# HumTemp_ESP32.net
KiCad netlist of a schematic drawn in Altium Designer
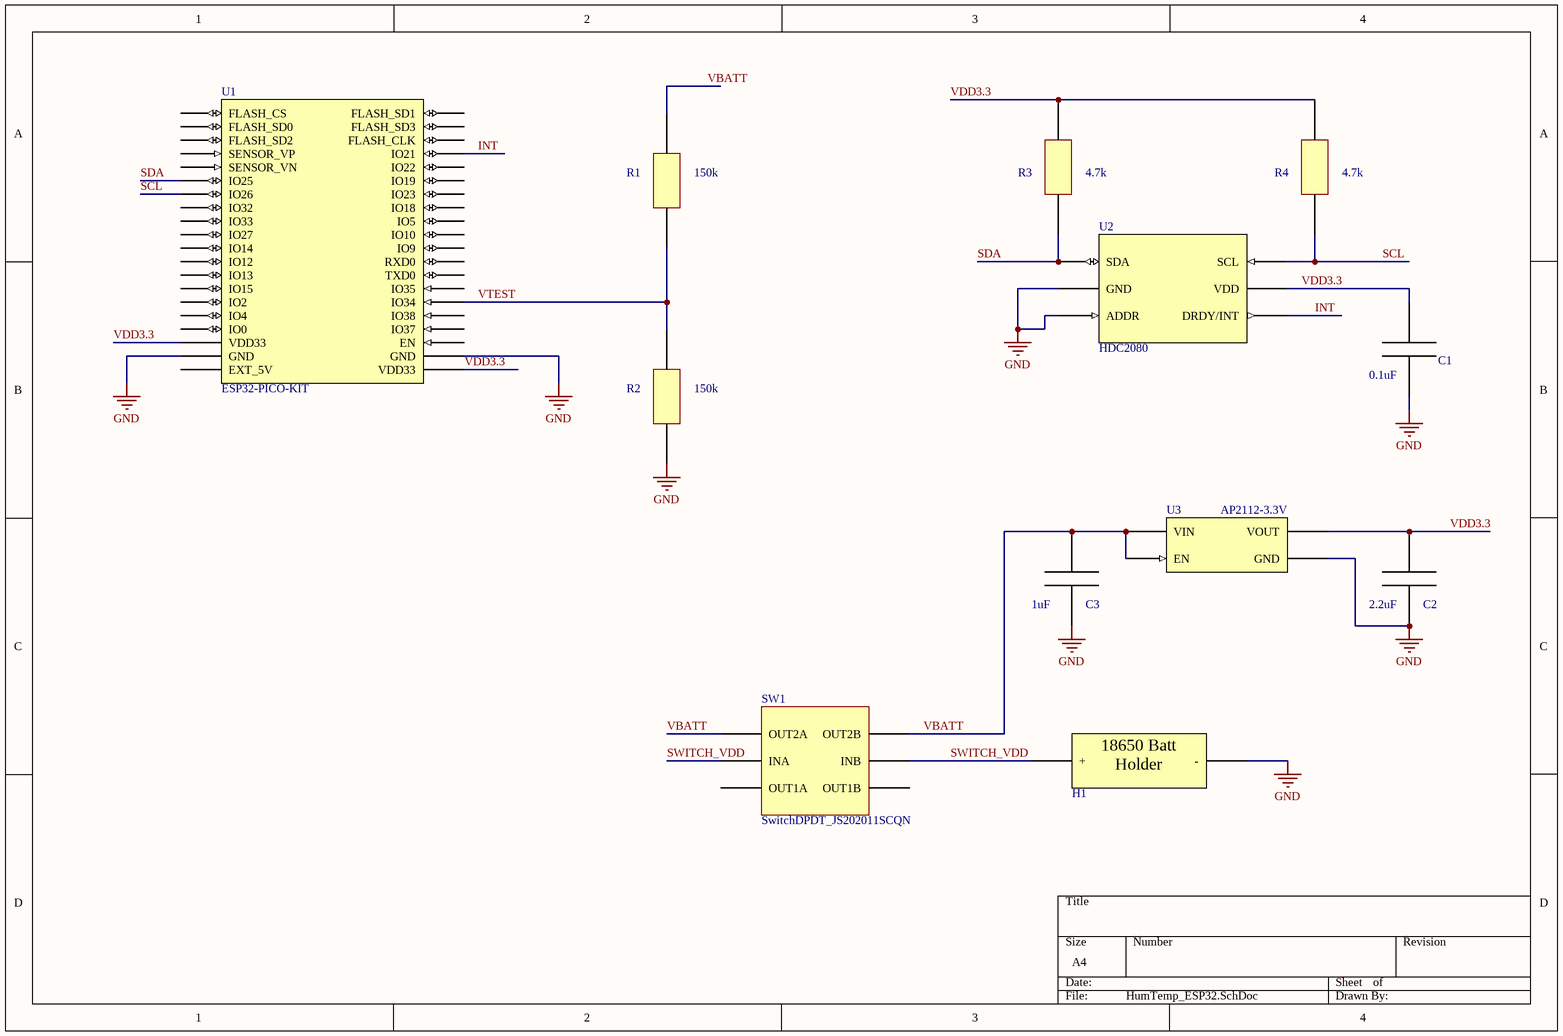
[diagram p0: HumTemp_ESP32.SchDoc]

(export (version "E")
  (design (tool "Eeschema 10.0.6"))
  (components
    (comp (ref "C1")
      (value "0.1uF")
      (footprint "CAPCERAMIC_SMD_2012M_0805I")
      (description "Ceramic SMD capacitor")
      (fields (field (name "Comment") "SMD Capacitor"))
      (libsource (lib "Capacitors") (part "capceramic_SMD"))
    )
    (comp (ref "C2")
      (value "2.2uF")
      (footprint "CAPCERAMIC_SMD_2012M_0805I")
      (description "Ceramic SMD capacitor")
      (fields (field (name "Comment") "SMD Capacitor"))
      (libsource (lib "Capacitors") (part "capceramic_SMD"))
    )
    (comp (ref "C3")
      (value "1uF")
      (footprint "CAPCERAMIC_SMD_2012M_0805I")
      (description "Ceramic SMD capacitor")
      (fields (field (name "Comment") "SMD Capacitor"))
      (libsource (lib "Capacitors") (part "capceramic_SMD"))
    )
    (comp (ref "H1")
      (value "18650 Battery holder - Keystone")
      (footprint "18650_BATTERYHOLDER")
      (libsource (lib "Connectors") (part "18650 Battery holder - Keystone"))
    )
    (comp (ref "R1")
      (value "150k")
      (footprint "RES_SMD_2012M-0805I")
      (fields (field (name "Comment") "SMD Resistor"))
      (libsource (lib "Resistors") (part "resistor_SMD"))
    )
    (comp (ref "R2")
      (value "150k")
      (footprint "RES_SMD_2012M-0805I")
      (fields (field (name "Comment") "SMD Resistor"))
      (libsource (lib "Resistors") (part "resistor_SMD"))
    )
    (comp (ref "R3")
      (value "4.7k")
      (footprint "RES_SMD_2012M-0805I")
      (fields (field (name "Comment") "SMD Resistor"))
      (libsource (lib "Resistors") (part "resistor_SMD"))
    )
    (comp (ref "R4")
      (value "4.7k")
      (footprint "RES_SMD_2012M-0805I")
      (fields (field (name "Comment") "SMD Resistor"))
      (libsource (lib "Resistors") (part "resistor_SMD"))
    )
    (comp (ref "SW1")
      (value "SwitchDPDT_JS202011SCQN")
      (footprint "SWITCHDPDT")
      (libsource (lib "Miscellaneous") (part "SwitchDPDT_JS202011SCQN"))
    )
    (comp (ref "U1")
      (value "ESP32-PICO-KIT")
      (footprint "ESP32-PICO-KIT")
      (libsource (lib "DevBoards") (part "ESP32-PICO-KIT"))
    )
    (comp (ref "U2")
      (value "HDC2080")
      (footprint "WSON6")
      (description "High precision humidity and temperature sensor")
      (libsource (lib "Sensors") (part "HDC2080"))
    )
    (comp (ref "U3")
      (value "AP2112-3.3V")
      (footprint "SOT95P285X110-5M")
      (description "AP2112 - 3.3V voltage regulator")
      (libsource (lib "Power_management") (part "AP2112-3.3V"))
    )
  )
  (nets
    (net (code "1") (name "/INT") (class "Default")
      (node (ref "U1") (pin "24") (pinfunction "IO21_24") (pintype "bidirectional"))
      (node (ref "U2") (pin "4") (pinfunction "DRDY/INT_4") (pintype "output"))
    )
    (net (code "2") (name "/SCL") (class "Default")
      (node (ref "R4") (pin "1") (pinfunction "1_1") (pintype "passive"))
      (node (ref "U1") (pin "7") (pinfunction "IO26_7") (pintype "bidirectional"))
      (node (ref "U2") (pin "6") (pinfunction "SCL_6") (pintype "input"))
    )
    (net (code "3") (name "/SDA") (class "Default")
      (node (ref "R3") (pin "1") (pinfunction "1_1") (pintype "passive"))
      (node (ref "U1") (pin "6") (pinfunction "IO25_6") (pintype "bidirectional"))
      (node (ref "U2") (pin "1") (pinfunction "SDA_1") (pintype "bidirectional"))
    )
    (net (code "4") (name "/SWITCH_VDD") (class "Default")
      (node (ref "H1") (pin "2") (pinfunction "+_2") (pintype "power_in"))
      (node (ref "SW1") (pin "1") (pinfunction "INA_1") (pintype "power_in"))
      (node (ref "SW1") (pin "4") (pinfunction "INB_4") (pintype "power_in"))
    )
    (net (code "5") (name "/VBATT") (class "Default")
      (node (ref "C3") (pin "2") (pinfunction "2_2") (pintype "passive"))
      (node (ref "R1") (pin "2") (pinfunction "2_2") (pintype "passive"))
      (node (ref "SW1") (pin "2") (pinfunction "OUT2A_2") (pintype "power_in"))
      (node (ref "SW1") (pin "5") (pinfunction "OUT2B_5") (pintype "power_in"))
      (node (ref "U3") (pin "1") (pinfunction "VIN_1") (pintype "power_in"))
      (node (ref "U3") (pin "3") (pinfunction "EN_3") (pintype "input"))
    )
    (net (code "6") (name "/VDD3.3") (class "Default")
      (node (ref "C1") (pin "2") (pinfunction "2_2") (pintype "passive"))
      (node (ref "C2") (pin "2") (pinfunction "2_2") (pintype "passive"))
      (node (ref "R3") (pin "2") (pinfunction "2_2") (pintype "passive"))
      (node (ref "R4") (pin "2") (pinfunction "2_2") (pintype "passive"))
      (node (ref "U1") (pin "18") (pinfunction "VDD33_18") (pintype "power_in"))
      (node (ref "U1") (pin "40") (pinfunction "VDD33_40") (pintype "power_in"))
      (node (ref "U2") (pin "5") (pinfunction "VDD_5") (pintype "power_in"))
      (node (ref "U3") (pin "5") (pinfunction "VOUT_5") (pintype "power_in"))
    )
    (net (code "7") (name "/VTEST") (class "Default")
      (node (ref "R1") (pin "1") (pinfunction "1_1") (pintype "passive"))
      (node (ref "R2") (pin "2") (pinfunction "2_2") (pintype "passive"))
      (node (ref "U1") (pin "35") (pinfunction "IO34_35") (pintype "input"))
    )
    (net (code "8") (name "GND") (class "Default")
      (node (ref "C1") (pin "1") (pinfunction "1_1") (pintype "passive"))
      (node (ref "C2") (pin "1") (pinfunction "1_1") (pintype "passive"))
      (node (ref "C3") (pin "1") (pinfunction "1_1") (pintype "passive"))
      (node (ref "H1") (pin "1") (pinfunction "-_1") (pintype "power_in"))
      (node (ref "R2") (pin "1") (pinfunction "1_1") (pintype "passive"))
      (node (ref "U1") (pin "19") (pinfunction "GND_19") (pintype "power_in"))
      (node (ref "U1") (pin "39") (pinfunction "GND_39") (pintype "power_in"))
      (node (ref "U2") (pin "2") (pinfunction "GND_2") (pintype "power_in"))
      (node (ref "U2") (pin "3") (pinfunction "ADDR_3") (pintype "input"))
      (node (ref "U3") (pin "2") (pinfunction "GND_2") (pintype "power_in"))
    )
    (net (code "9") (name "unconnected-(SW1-OUT1A-Pad0)") (class "Default")
      (node (ref "SW1") (pin "0") (pinfunction "OUT1A_0") (pintype "power_in"))
    )
    (net (code "10") (name "unconnected-(SW1-OUT1B-Pad3)") (class "Default")
      (node (ref "SW1") (pin "3") (pinfunction "OUT1B_3") (pintype "power_in"))
    )
    (net (code "11") (name "unconnected-(U1-EN-Pad38)") (class "Default")
      (node (ref "U1") (pin "38") (pinfunction "EN_38") (pintype "input"))
    )
    (net (code "12") (name "unconnected-(U1-EXT_5V-Pad20)") (class "Default")
      (node (ref "U1") (pin "20") (pinfunction "EXT_5V_20") (pintype "power_in"))
    )
    (net (code "13") (name "unconnected-(U1-FLASH_CLK-Pad23)") (class "Default")
      (node (ref "U1") (pin "23") (pinfunction "FLASH_CLK_23") (pintype "bidirectional"))
    )
    (net (code "14") (name "unconnected-(U1-FLASH_CS-Pad1)") (class "Default")
      (node (ref "U1") (pin "1") (pinfunction "FLASH_CS_1") (pintype "bidirectional"))
    )
    (net (code "15") (name "unconnected-(U1-FLASH_SD0-Pad2)") (class "Default")
      (node (ref "U1") (pin "2") (pinfunction "FLASH_SD0_2") (pintype "bidirectional"))
    )
    (net (code "16") (name "unconnected-(U1-FLASH_SD1-Pad21)") (class "Default")
      (node (ref "U1") (pin "21") (pinfunction "FLASH_SD1_21") (pintype "bidirectional"))
    )
    (net (code "17") (name "unconnected-(U1-FLASH_SD2-Pad3)") (class "Default")
      (node (ref "U1") (pin "3") (pinfunction "FLASH_SD2_3") (pintype "bidirectional"))
    )
    (net (code "18") (name "unconnected-(U1-FLASH_SD3-Pad22)") (class "Default")
      (node (ref "U1") (pin "22") (pinfunction "FLASH_SD3_22") (pintype "bidirectional"))
    )
    (net (code "19") (name "unconnected-(U1-IO0-Pad17)") (class "Default")
      (node (ref "U1") (pin "17") (pinfunction "IO0_17") (pintype "bidirectional"))
    )
    (net (code "20") (name "unconnected-(U1-IO2-Pad15)") (class "Default")
      (node (ref "U1") (pin "15") (pinfunction "IO2_15") (pintype "bidirectional"))
    )
    (net (code "21") (name "unconnected-(U1-IO4-Pad16)") (class "Default")
      (node (ref "U1") (pin "16") (pinfunction "IO4_16") (pintype "bidirectional"))
    )
    (net (code "22") (name "unconnected-(U1-IO5-Pad29)") (class "Default")
      (node (ref "U1") (pin "29") (pinfunction "IO5_29") (pintype "bidirectional"))
    )
    (net (code "23") (name "unconnected-(U1-IO9-Pad31)") (class "Default")
      (node (ref "U1") (pin "31") (pinfunction "IO9_31") (pintype "bidirectional"))
    )
    (net (code "24") (name "unconnected-(U1-IO10-Pad30)") (class "Default")
      (node (ref "U1") (pin "30") (pinfunction "IO10_30") (pintype "bidirectional"))
    )
    (net (code "25") (name "unconnected-(U1-IO12-Pad12)") (class "Default")
      (node (ref "U1") (pin "12") (pinfunction "IO12_12") (pintype "bidirectional"))
    )
    (net (code "26") (name "unconnected-(U1-IO13-Pad13)") (class "Default")
      (node (ref "U1") (pin "13") (pinfunction "IO13_13") (pintype "bidirectional"))
    )
    (net (code "27") (name "unconnected-(U1-IO14-Pad11)") (class "Default")
      (node (ref "U1") (pin "11") (pinfunction "IO14_11") (pintype "bidirectional"))
    )
    (net (code "28") (name "unconnected-(U1-IO15-Pad14)") (class "Default")
      (node (ref "U1") (pin "14") (pinfunction "IO15_14") (pintype "bidirectional"))
    )
    (net (code "29") (name "unconnected-(U1-IO18-Pad28)") (class "Default")
      (node (ref "U1") (pin "28") (pinfunction "IO18_28") (pintype "bidirectional"))
    )
    (net (code "30") (name "unconnected-(U1-IO19-Pad26)") (class "Default")
      (node (ref "U1") (pin "26") (pinfunction "IO19_26") (pintype "bidirectional"))
    )
    (net (code "31") (name "unconnected-(U1-IO22-Pad25)") (class "Default")
      (node (ref "U1") (pin "25") (pinfunction "IO22_25") (pintype "bidirectional"))
    )
    (net (code "32") (name "unconnected-(U1-IO23-Pad27)") (class "Default")
      (node (ref "U1") (pin "27") (pinfunction "IO23_27") (pintype "bidirectional"))
    )
    (net (code "33") (name "unconnected-(U1-IO27-Pad10)") (class "Default")
      (node (ref "U1") (pin "10") (pinfunction "IO27_10") (pintype "bidirectional"))
    )
    (net (code "34") (name "unconnected-(U1-IO32-Pad8)") (class "Default")
      (node (ref "U1") (pin "8") (pinfunction "IO32_8") (pintype "bidirectional"))
    )
    (net (code "35") (name "unconnected-(U1-IO33-Pad9)") (class "Default")
      (node (ref "U1") (pin "9") (pinfunction "IO33_9") (pintype "bidirectional"))
    )
    (net (code "36") (name "unconnected-(U1-IO35-Pad34)") (class "Default")
      (node (ref "U1") (pin "34") (pinfunction "IO35_34") (pintype "input"))
    )
    (net (code "37") (name "unconnected-(U1-IO37-Pad37)") (class "Default")
      (node (ref "U1") (pin "37") (pinfunction "IO37_37") (pintype "input"))
    )
    (net (code "38") (name "unconnected-(U1-IO38-Pad36)") (class "Default")
      (node (ref "U1") (pin "36") (pinfunction "IO38_36") (pintype "input"))
    )
    (net (code "39") (name "unconnected-(U1-RXD0-Pad32)") (class "Default")
      (node (ref "U1") (pin "32") (pinfunction "RXD0_32") (pintype "bidirectional"))
    )
    (net (code "40") (name "unconnected-(U1-SENSOR_VN-Pad5)") (class "Default")
      (node (ref "U1") (pin "5") (pinfunction "SENSOR_VN_5") (pintype "input"))
    )
    (net (code "41") (name "unconnected-(U1-SENSOR_VP-Pad4)") (class "Default")
      (node (ref "U1") (pin "4") (pinfunction "SENSOR_VP_4") (pintype "input"))
    )
    (net (code "42") (name "unconnected-(U1-TXD0-Pad33)") (class "Default")
      (node (ref "U1") (pin "33") (pinfunction "TXD0_33") (pintype "bidirectional"))
    )
  )
)
